# 04_POWER_V1-0.net
KiCad netlist of a schematic drawn in Altium Designer
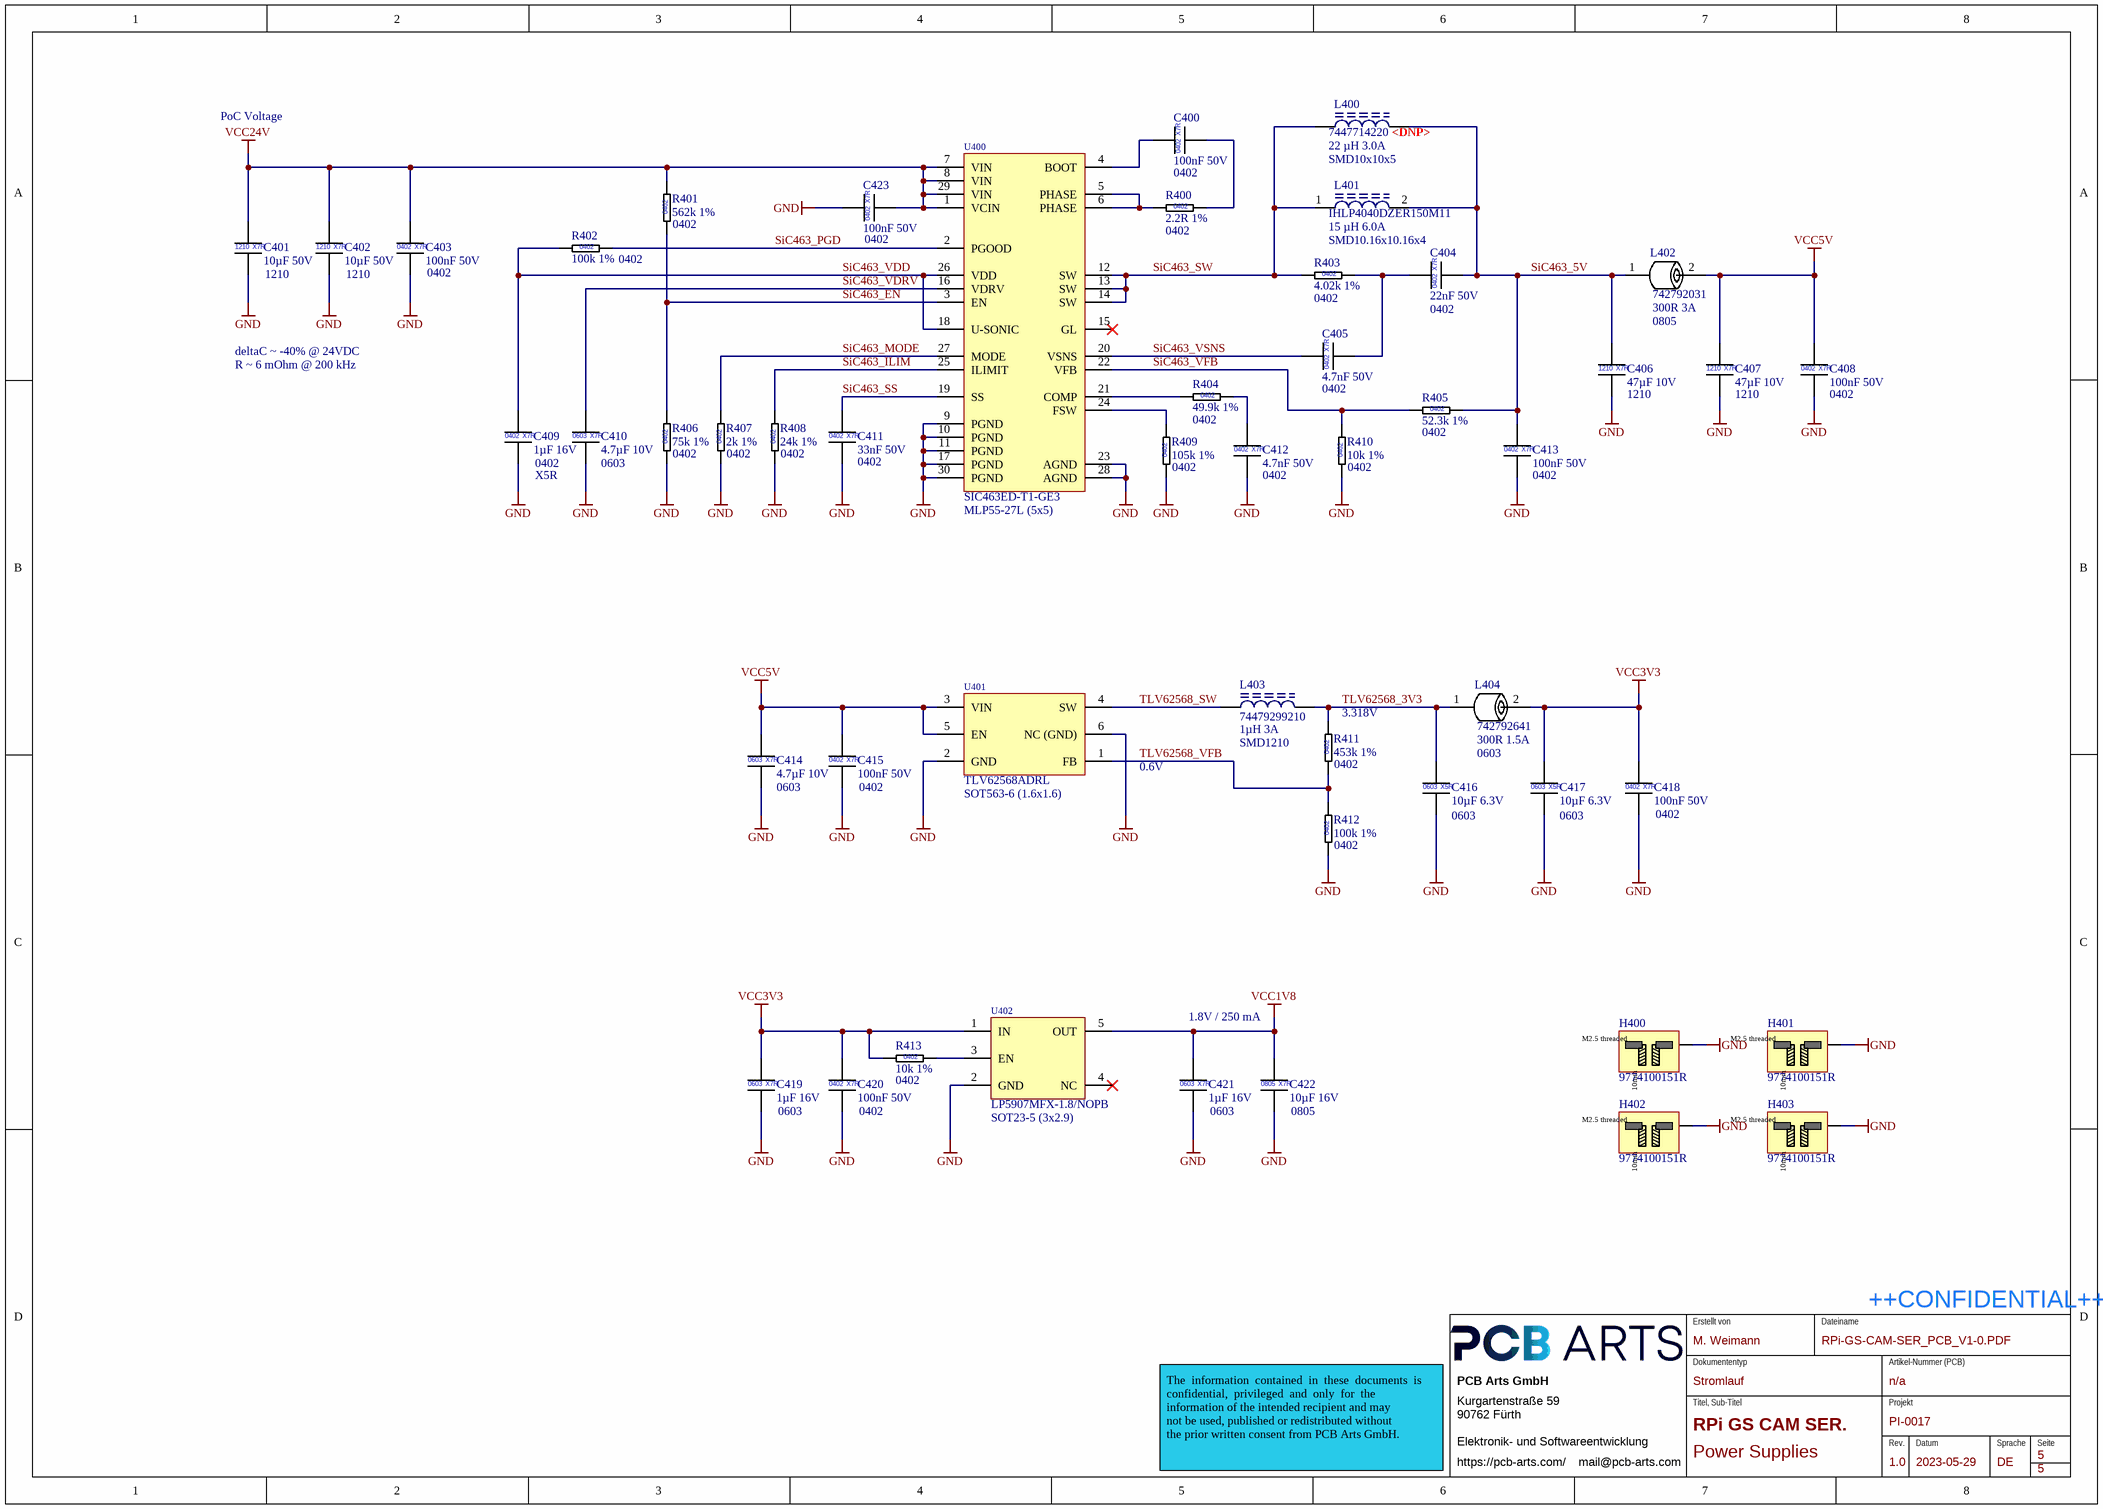
[diagram p0: 04_POWER_V1-0.SchDoc]

(export (version "E")
  (design (tool "Eeschema 10.0.6"))
  (components
    (comp (ref "C400")
      (value "100nF 50V")
      (footprint "Cap:CAP_0402_L")
      (description "Multilayer Ceramic Capacitors MLCC - SMD/SMT 0402 50VDC")
      (libsource (lib "") (part "CAP_0402_100nF_50V_1"))
    )
    (comp (ref "C401")
      (value "10µF 50V")
      (footprint "Cap:CAP_1210")
      (description "Multilayer Ceramic Capacitors MLCC - SMD/SMT 10 uF 50 VDC 10% 1210 X7R")
      (libsource (lib "Cap") (part "CAP_1210_10µF_50V_X7R_10%"))
    )
    (comp (ref "C402")
      (value "10µF 50V")
      (footprint "Cap:CAP_1210")
      (description "Multilayer Ceramic Capacitors MLCC - SMD/SMT 10 uF 50 VDC 10% 1210 X7R")
      (libsource (lib "Cap") (part "CAP_1210_10µF_50V_X7R_10%"))
    )
    (comp (ref "C403")
      (value "100nF 50V")
      (footprint "Cap:CAP_0402_L")
      (description "Multilayer Ceramic Capacitors MLCC - SMD/SMT 0402 50VDC")
      (libsource (lib "Cap") (part "CAP_0402_100nF_50V"))
    )
    (comp (ref "C404")
      (value "22nF 50V")
      (footprint "Cap:CAP_0402_L")
      (description "Multilayer Ceramic Capacitors MLCC - SMD/SMT 0402 50VDC")
      (libsource (lib "Cap") (part "CAP_0402_22nF_50V"))
    )
    (comp (ref "C405")
      (value "4.7nF 50V")
      (footprint "Cap:CAP_0402_L")
      (description "Multilayer Ceramic Capacitors MLCC - SMD/SMT 50V 0.022uF X7R 0402 10%")
      (libsource (lib "") (part "CAP_0402_4.7nF_50V_X7R_10%_1"))
    )
    (comp (ref "C406")
      (value "47µF 10V")
      (footprint "Cap:CAP_1210")
      (description "Multilayer Ceramic Capacitors MLCC - SMD/SMT 47 uF 10 VDC 10% 1210 X7R")
      (libsource (lib "Cap") (part "CAP_1210_47µF_10V_X7R_10%"))
    )
    (comp (ref "C407")
      (value "47µF 10V")
      (footprint "Cap:CAP_1210")
      (description "Multilayer Ceramic Capacitors MLCC - SMD/SMT 47 uF 10 VDC 10% 1210 X7R")
      (libsource (lib "Cap") (part "CAP_1210_47µF_10V_X7R_10%"))
    )
    (comp (ref "C408")
      (value "100nF 50V")
      (footprint "Cap:CAP_0402_L")
      (description "Multilayer Ceramic Capacitors MLCC - SMD/SMT 0402 50VDC")
      (libsource (lib "Cap") (part "CAP_0402_100nF_50V"))
    )
    (comp (ref "C409")
      (value "1µF 16V")
      (footprint "Cap:CAP_0402_L")
      (description "Multilayer Ceramic Capacitors MLCC - SMD/SMT 0402 16VDC")
      (libsource (lib "Cap") (part "CAP_0402_1µF_16V"))
    )
    (comp (ref "C410")
      (value "4.7µF 10V")
      (footprint "Cap:CAP_0603_L")
      (description "Multilayer Ceramic Capacitors MLCC - SMD/SMT 4.7 uF 10 VDC 10% 0603 X7R")
      (libsource (lib "Cap") (part "CAP_0603_4.7µF_10V_X7R_10%"))
    )
    (comp (ref "C411")
      (value "33nF 50V")
      (footprint "Cap:CAP_0402_L")
      (description "Multilayer Ceramic Capacitors MLCC - SMD/SMT 0402 50VDC")
      (libsource (lib "Cap") (part "CAP_0402_33nF_50V"))
    )
    (comp (ref "C412")
      (value "4.7nF 50V")
      (footprint "Cap:CAP_0402_L")
      (description "Multilayer Ceramic Capacitors MLCC - SMD/SMT 50V 0.022uF X7R 0402 10%")
      (libsource (lib "Cap") (part "CAP_0402_4.7nF_50V_X7R_10%"))
    )
    (comp (ref "C413")
      (value "100nF 50V")
      (footprint "Cap:CAP_0402_L")
      (description "Multilayer Ceramic Capacitors MLCC - SMD/SMT 0402 50VDC")
      (libsource (lib "Cap") (part "CAP_0402_100nF_50V"))
    )
    (comp (ref "C414")
      (value "4.7µF 10V")
      (footprint "Cap:CAP_0603_L")
      (description "Multilayer Ceramic Capacitors MLCC - SMD/SMT 4.7 uF 10 VDC 10% 0603 X7R")
      (libsource (lib "Cap") (part "CAP_0603_4.7µF_10V_X7R_10%"))
    )
    (comp (ref "C415")
      (value "100nF 50V")
      (footprint "Cap:CAP_0402_L")
      (description "Multilayer Ceramic Capacitors MLCC - SMD/SMT 0402 50VDC")
      (libsource (lib "Cap") (part "CAP_0402_100nF_50V"))
    )
    (comp (ref "C416")
      (value "10µF 6.3V")
      (footprint "Cap:CAP_0603_L")
      (description "Multilayer Ceramic Capacitors MLCC - SMD/SMT 0603 6.3VDC")
      (libsource (lib "Cap") (part "CAP_0603_10µF_6.3V"))
    )
    (comp (ref "C417")
      (value "10µF 6.3V")
      (footprint "Cap:CAP_0603_L")
      (description "Multilayer Ceramic Capacitors MLCC - SMD/SMT 0603 6.3VDC")
      (libsource (lib "Cap") (part "CAP_0603_10µF_6.3V"))
    )
    (comp (ref "C418")
      (value "100nF 50V")
      (footprint "Cap:CAP_0402_L")
      (description "Multilayer Ceramic Capacitors MLCC - SMD/SMT 0402 50VDC")
      (libsource (lib "Cap") (part "CAP_0402_100nF_50V"))
    )
    (comp (ref "C419")
      (value "1µF 16V")
      (footprint "CAP_0603_L")
      (description "Multilayer Ceramic Capacitors MLCC - SMD/SMT 0603 16VDC 1uF 10% X7R 0.8mm")
      (libsource (lib "Cap") (part "CAP_0603_1µF_16V_X7R_10%"))
    )
    (comp (ref "C420")
      (value "100nF 50V")
      (footprint "Cap:CAP_0402_L")
      (description "Multilayer Ceramic Capacitors MLCC - SMD/SMT 0402 50VDC")
      (libsource (lib "Cap") (part "CAP_0402_100nF_50V"))
    )
    (comp (ref "C421")
      (value "1µF 16V")
      (footprint "CAP_0603_L")
      (description "Multilayer Ceramic Capacitors MLCC - SMD/SMT 0603 16VDC 1uF 10% X7R 0.8mm")
      (libsource (lib "Cap") (part "CAP_0603_1µF_16V_X7R_10%"))
    )
    (comp (ref "C422")
      (value "10µF 16V")
      (footprint "Cap:CAP_0805")
      (description "Multilayer Ceramic Capacitors MLCC - SMD/SMT 16V 10uF X7R 0805 10%")
      (libsource (lib "Cap") (part "CAP_0805_10µF_16V_X7R_10%"))
    )
    (comp (ref "C423")
      (value "100nF 50V")
      (footprint "Cap:CAP_0402_L")
      (description "Multilayer Ceramic Capacitors MLCC - SMD/SMT 0402 50VDC")
      (libsource (lib "") (part "CAP_0402_100nF_50V_1"))
    )
    (comp (ref "H400")
      (value "9774100151R")
      (footprint "Electro_Mech:9774100151R")
      (description "Würth Standoff M2.5 h:10mm 9774050151R")
      (libsource (lib "Electro_Mech") (part "Würth Standoff M2.5 h{colon}10mm"))
    )
    (comp (ref "H401")
      (value "9774100151R")
      (footprint "Electro_Mech:9774100151R")
      (description "Würth Standoff M2.5 h:10mm 9774050151R")
      (libsource (lib "Electro_Mech") (part "Würth Standoff M2.5 h{colon}10mm"))
    )
    (comp (ref "H402")
      (value "9774100151R")
      (footprint "Electro_Mech:9774100151R")
      (description "Würth Standoff M2.5 h:10mm 9774050151R")
      (libsource (lib "Electro_Mech") (part "Würth Standoff M2.5 h{colon}10mm"))
    )
    (comp (ref "H403")
      (value "9774100151R")
      (footprint "Electro_Mech:9774100151R")
      (description "Würth Standoff M2.5 h:10mm 9774050151R")
      (libsource (lib "Electro_Mech") (part "Würth Standoff M2.5 h{colon}10mm"))
    )
    (comp (ref "L400")
      (value "7447714220")
      (footprint "WE-PD_1050")
      (description "Power Inductors - SMD WE-PD 22uH 3A DCR=50mOhms")
      (libsource (lib "Indc") (part "7447714220_22uH_20%_3.0A_50mΩ_SMD"))
    )
    (comp (ref "L401")
      (value "IHLP4040DZER150M11")
      (footprint "IHLP-4040DZ-11")
      (description "15uH ±20% 6A 45mΩ SMD,10.16x10.16x4mm Power Inductor")
      (libsource (lib "Indc") (part "IHLP4040DZER150M11_15uH_20%_6.0A_45mΩ_SMD"))
    )
    (comp (ref "L402")
      (value "742792031")
      (footprint "indc:L_0805")
      (description "Ferrite Beads WE-CBF 0805 200MHz 300Ohm 3000mA AEC-Q200")
      (libsource (lib "Indc") (part "742792031 _Ferrite_Beads_0805_300Ohms_3000mA"))
    )
    (comp (ref "L403")
      (value "74479299210")
      (footprint "WE-PMCI_1210")
      (description "Fixed Power Inductor - SMD WE-PMCI 1210 1.0uH 3A 38mOhms 30%Tol")
      (libsource (lib "Indc") (part "74479299210_Fixed_Inductors_1.0uH_30%_3A_SMD1210"))
    )
    (comp (ref "L404")
      (value "742792641")
      (footprint "Indc:L_0603")
      (description "Ferrite Beads WE-CBF 0603 100MHz 300Ohm 2000mA AEC-Q200")
      (libsource (lib "Indc") (part "742792641_Ferrite_Beads_0603_300Ohms_1500mA"))
    )
    (comp (ref "R400")
      (value "2.2R 1%")
      (footprint "Res:RES_0402_L")
      (description "Thick Film Resistors - SMD 2.2Ohm 1%")
      (libsource (lib "Res") (part "RES_0402_2.2R_1%"))
    )
    (comp (ref "R401")
      (value "562k 1%")
      (footprint "Res:RES_0402_L")
      (description "Thick Film Resistors - SMD 562kOhms 62.5mW 0402 1%")
      (libsource (lib "Res") (part "RES_0402_562k_1%"))
    )
    (comp (ref "R402")
      (value "100k 1%")
      (footprint "Res:RES_0402_L")
      (description "Thick Film Resistors - SMD 100kOhm 1%")
      (libsource (lib "Res") (part "RES_0402_100k_1%"))
    )
    (comp (ref "R403")
      (value "4.02k 1%")
      (footprint "Res:RES_0402_L")
      (description "Thick Film Resistors - SMD 4.02kOhm 1%")
      (libsource (lib "Res") (part "RES_0402_4.02k_1%"))
    )
    (comp (ref "R404")
      (value "49.9k 1%")
      (footprint "Res:RES_0402_L")
      (description "Thick Film Resistors - SMD 49.9kOhm 1%")
      (libsource (lib "Res") (part "RES_0402_49.9k_1%"))
    )
    (comp (ref "R405")
      (value "52.3k 1%")
      (footprint "Res:RES_0402_L")
      (description "Thick Film Resistors - SMD 52.3kOhm 1%")
      (libsource (lib "Res") (part "RES_0402_52.3k_1%"))
    )
    (comp (ref "R406")
      (value "75k 1%")
      (footprint "Res:RES_0402_L")
      (description "Thick Film Resistors - SMD 75kOhm 1%")
      (libsource (lib "Res") (part "RES_0402_75k_1%"))
    )
    (comp (ref "R407")
      (value "2k 1%")
      (footprint "Res:RES_0402_L")
      (description "Thick Film Resistors - SMD 2 kOhms 62.5mW 0402 1%")
      (libsource (lib "Res") (part "RES_0402_2k_1%"))
    )
    (comp (ref "R408")
      (value "24k 1%")
      (footprint "Res:RES_0402_L")
      (description "Thick Film Resistors - SMD 24kOhm 1%")
      (libsource (lib "Res") (part "RES_0402_24k_1%"))
    )
    (comp (ref "R409")
      (value "105k 1%")
      (footprint "Res:RES_0402_L")
      (description "Thick Film Resistors - SMD 105kOhm 1%")
      (libsource (lib "Res") (part "RES_0402_105k_1%"))
    )
    (comp (ref "R410")
      (value "10k 1%")
      (footprint "Res:RES_0402_L")
      (description "Thick Film Resistors - SMD 10kOhm 1%")
      (libsource (lib "Res") (part "RES_0402_10k_1%"))
    )
    (comp (ref "R411")
      (value "453k 1%")
      (footprint "RES_0402_L")
      (description "Thick Film Resistors - SMD 1/16watt 453Kohms 1%")
      (libsource (lib "Res") (part "RES_0402_453k_1%"))
    )
    (comp (ref "R412")
      (value "100k 1%")
      (footprint "Res:RES_0402_L")
      (description "Thick Film Resistors - SMD 100kOhm 1%")
      (libsource (lib "Res") (part "RES_0402_100k_1%"))
    )
    (comp (ref "R413")
      (value "10k 1%")
      (footprint "Res:RES_0402_L")
      (description "Thick Film Resistors - SMD 10kOhm 1%")
      (libsource (lib "Res") (part "RES_0402_10k_1%"))
    )
    (comp (ref "U400")
      (value "SIC463ED-T1-GE3")
      (footprint "VISHAY_MLP55-27L")
      (description "Switching Voltage Regulators 4A, 4.5-60V buck reg 100kHZ to 2MHz; 5 mm x 5 mm MLP55-27L package")
      (libsource (lib "Power") (part "SIC463ED-T1-GE3_Switching_Voltage_Regulator_4A"))
    )
    (comp (ref "U401")
      (value "TLV62568ADRL")
      (footprint "Power:SON50P150X80-6N")
      (description "Step Down Converter with Forced PWM in SOT563 Package")
      (libsource (lib "Power") (part "TLV62568ADRL_Step Down Converter 1A; 2A"))
    )
    (comp (ref "U402")
      (value "LP5907MFX-1.8/NOPB")
      (footprint "SOT95P285X140-5N")
      (description "LDO Spannungs-Regulator 250mA Ultra-Lo Noise LDO Reg SOT23-5")
      (libsource (lib "Power") (part "LP5907MFX-1.8/NOPB_LDO_Voltage_Regulators_250mA"))
    )
  )
  (nets
    (net (code "1") (name "/SiC463_5V") (class "Default")
      (node (ref "C404") (pin "2") (pinfunction "2_2") (pintype "passive"))
      (node (ref "C406") (pin "1") (pinfunction "1_1") (pintype "passive"))
      (node (ref "C413") (pin "1") (pinfunction "1_1") (pintype "passive"))
      (node (ref "L400") (pin "2") (pinfunction "2_2") (pintype "passive"))
      (node (ref "L401") (pin "2") (pinfunction "2_2") (pintype "passive"))
      (node (ref "L402") (pin "1") (pinfunction "1_1") (pintype "passive"))
      (node (ref "R405") (pin "2") (pinfunction "2_2") (pintype "passive"))
    )
    (net (code "2") (name "/SiC463_EN") (class "Default")
      (node (ref "R401") (pin "1") (pinfunction "1_1") (pintype "passive"))
      (node (ref "R406") (pin "2") (pinfunction "2_2") (pintype "passive"))
      (node (ref "U400") (pin "3") (pinfunction "EN_3") (pintype "passive"))
    )
    (net (code "3") (name "/SiC463_ILIM") (class "Default")
      (node (ref "R408") (pin "2") (pinfunction "2_2") (pintype "passive"))
      (node (ref "U400") (pin "25") (pinfunction "ILIMIT_25") (pintype "passive"))
    )
    (net (code "4") (name "/SiC463_MODE") (class "Default")
      (node (ref "R407") (pin "2") (pinfunction "2_2") (pintype "passive"))
      (node (ref "U400") (pin "27") (pinfunction "MODE_27") (pintype "passive"))
    )
    (net (code "5") (name "/SiC463_PGD") (class "Default")
      (node (ref "R402") (pin "2") (pinfunction "2_2") (pintype "passive"))
      (node (ref "U400") (pin "2") (pinfunction "PGOOD_2") (pintype "passive"))
    )
    (net (code "6") (name "/SiC463_SS") (class "Default")
      (node (ref "C411") (pin "1") (pinfunction "1_1") (pintype "passive"))
      (node (ref "U400") (pin "19") (pinfunction "SS_19") (pintype "passive"))
    )
    (net (code "7") (name "/SiC463_SW") (class "Default")
      (node (ref "L400") (pin "1") (pinfunction "1_1") (pintype "passive"))
      (node (ref "L401") (pin "1") (pinfunction "1_1") (pintype "passive"))
      (node (ref "R403") (pin "1") (pinfunction "1_1") (pintype "passive"))
      (node (ref "U400") (pin "12") (pinfunction "SW_12") (pintype "passive"))
      (node (ref "U400") (pin "13") (pinfunction "SW_13") (pintype "passive"))
      (node (ref "U400") (pin "14") (pinfunction "SW_14") (pintype "passive"))
    )
    (net (code "8") (name "/SiC463_VDD") (class "Default")
      (node (ref "C409") (pin "1") (pinfunction "1_1") (pintype "passive"))
      (node (ref "R402") (pin "1") (pinfunction "1_1") (pintype "passive"))
      (node (ref "U400") (pin "18") (pinfunction "U-SONIC_18") (pintype "passive"))
      (node (ref "U400") (pin "26") (pinfunction "VDD_26") (pintype "passive"))
    )
    (net (code "9") (name "/SiC463_VDRV") (class "Default")
      (node (ref "C410") (pin "1") (pinfunction "1_1") (pintype "passive"))
      (node (ref "U400") (pin "16") (pinfunction "VDRV_16") (pintype "passive"))
    )
    (net (code "10") (name "/SiC463_VFB") (class "Default")
      (node (ref "R405") (pin "1") (pinfunction "1_1") (pintype "passive"))
      (node (ref "R410") (pin "2") (pinfunction "2_2") (pintype "passive"))
      (node (ref "U400") (pin "22") (pinfunction "VFB_22") (pintype "passive"))
    )
    (net (code "11") (name "/SiC463_VSNS") (class "Default")
      (node (ref "C405") (pin "1") (pinfunction "1_1") (pintype "passive"))
      (node (ref "U400") (pin "20") (pinfunction "VSNS_20") (pintype "passive"))
    )
    (net (code "12") (name "/TLV62568_3V3") (class "Default")
      (node (ref "C416") (pin "1") (pinfunction "1_1") (pintype "passive"))
      (node (ref "L403") (pin "2") (pinfunction "2_2") (pintype "passive"))
      (node (ref "L404") (pin "1") (pinfunction "1_1") (pintype "passive"))
      (node (ref "R411") (pin "2") (pinfunction "2_2") (pintype "passive"))
    )
    (net (code "13") (name "/TLV62568_SW") (class "Default")
      (node (ref "L403") (pin "1") (pinfunction "1_1") (pintype "passive"))
      (node (ref "U401") (pin "4") (pinfunction "SW_4") (pintype "passive"))
    )
    (net (code "14") (name "/TLV62568_VFB") (class "Default")
      (node (ref "R411") (pin "1") (pinfunction "1_1") (pintype "passive"))
      (node (ref "R412") (pin "2") (pinfunction "2_2") (pintype "passive"))
      (node (ref "U401") (pin "1") (pinfunction "FB_1") (pintype "passive"))
    )
    (net (code "15") (name "GND") (class "Default")
      (node (ref "C401") (pin "2") (pinfunction "2_2") (pintype "passive"))
      (node (ref "C402") (pin "2") (pinfunction "2_2") (pintype "passive"))
      (node (ref "C403") (pin "2") (pinfunction "2_2") (pintype "passive"))
      (node (ref "C406") (pin "2") (pinfunction "2_2") (pintype "passive"))
      (node (ref "C407") (pin "2") (pinfunction "2_2") (pintype "passive"))
      (node (ref "C408") (pin "2") (pinfunction "2_2") (pintype "passive"))
      (node (ref "C409") (pin "2") (pinfunction "2_2") (pintype "passive"))
      (node (ref "C410") (pin "2") (pinfunction "2_2") (pintype "passive"))
      (node (ref "C411") (pin "2") (pinfunction "2_2") (pintype "passive"))
      (node (ref "C412") (pin "2") (pinfunction "2_2") (pintype "passive"))
      (node (ref "C413") (pin "2") (pinfunction "2_2") (pintype "passive"))
      (node (ref "C414") (pin "2") (pinfunction "2_2") (pintype "passive"))
      (node (ref "C415") (pin "2") (pinfunction "2_2") (pintype "passive"))
      (node (ref "C416") (pin "2") (pinfunction "2_2") (pintype "passive"))
      (node (ref "C417") (pin "2") (pinfunction "2_2") (pintype "passive"))
      (node (ref "C418") (pin "2") (pinfunction "2_2") (pintype "passive"))
      (node (ref "C419") (pin "2") (pinfunction "2_2") (pintype "passive"))
      (node (ref "C420") (pin "2") (pinfunction "2_2") (pintype "passive"))
      (node (ref "C421") (pin "2") (pinfunction "2_2") (pintype "passive"))
      (node (ref "C422") (pin "2") (pinfunction "2_2") (pintype "passive"))
      (node (ref "C423") (pin "1") (pinfunction "1_1") (pintype "passive"))
      (node (ref "H400") (pin "1") (pinfunction "1_1") (pintype "passive"))
      (node (ref "H401") (pin "1") (pinfunction "1_1") (pintype "passive"))
      (node (ref "H402") (pin "1") (pinfunction "1_1") (pintype "passive"))
      (node (ref "H403") (pin "1") (pinfunction "1_1") (pintype "passive"))
      (node (ref "R406") (pin "1") (pinfunction "1_1") (pintype "passive"))
      (node (ref "R407") (pin "1") (pinfunction "1_1") (pintype "passive"))
      (node (ref "R408") (pin "1") (pinfunction "1_1") (pintype "passive"))
      (node (ref "R409") (pin "1") (pinfunction "1_1") (pintype "passive"))
      (node (ref "R410") (pin "1") (pinfunction "1_1") (pintype "passive"))
      (node (ref "R412") (pin "1") (pinfunction "1_1") (pintype "passive"))
      (node (ref "U400") (pin "10") (pinfunction "PGND_10") (pintype "passive"))
      (node (ref "U400") (pin "11") (pinfunction "PGND_11") (pintype "passive"))
      (node (ref "U400") (pin "17") (pinfunction "PGND_17") (pintype "passive"))
      (node (ref "U400") (pin "23") (pinfunction "AGND_23") (pintype "passive"))
      (node (ref "U400") (pin "28") (pinfunction "AGND_28") (pintype "passive"))
      (node (ref "U400") (pin "30") (pinfunction "PGND_30") (pintype "passive"))
      (node (ref "U400") (pin "9") (pinfunction "PGND_9") (pintype "passive"))
      (node (ref "U401") (pin "2") (pinfunction "GND_2") (pintype "passive"))
      (node (ref "U401") (pin "6") (pinfunction "NC_(GND)_6") (pintype "passive"))
      (node (ref "U402") (pin "2") (pinfunction "GND_2") (pintype "passive"))
    )
    (net (code "16") (name "Net-(C400-Pad2)") (class "Default")
      (node (ref "C400") (pin "2") (pinfunction "2_2") (pintype "passive"))
      (node (ref "R400") (pin "2") (pinfunction "2_2") (pintype "passive"))
    )
    (net (code "17") (name "Net-(C404-Pad1)") (class "Default")
      (node (ref "C404") (pin "1") (pinfunction "1_1") (pintype "passive"))
      (node (ref "C405") (pin "2") (pinfunction "2_2") (pintype "passive"))
      (node (ref "R403") (pin "2") (pinfunction "2_2") (pintype "passive"))
    )
    (net (code "18") (name "Net-(C412-Pad1)") (class "Default")
      (node (ref "C412") (pin "1") (pinfunction "1_1") (pintype "passive"))
      (node (ref "R404") (pin "2") (pinfunction "2_2") (pintype "passive"))
    )
    (net (code "19") (name "Net-(R400-Pad1)") (class "Default")
      (node (ref "R400") (pin "1") (pinfunction "1_1") (pintype "passive"))
      (node (ref "U400") (pin "5") (pinfunction "PHASE_5") (pintype "passive"))
      (node (ref "U400") (pin "6") (pinfunction "PHASE_6") (pintype "passive"))
    )
    (net (code "20") (name "Net-(U400-BOOT)") (class "Default")
      (node (ref "C400") (pin "1") (pinfunction "1_1") (pintype "passive"))
      (node (ref "U400") (pin "4") (pinfunction "BOOT_4") (pintype "passive"))
    )
    (net (code "21") (name "Net-(U400-COMP)") (class "Default")
      (node (ref "R404") (pin "1") (pinfunction "1_1") (pintype "passive"))
      (node (ref "U400") (pin "21") (pinfunction "COMP_21") (pintype "passive"))
    )
    (net (code "22") (name "Net-(U400-FSW)") (class "Default")
      (node (ref "R409") (pin "2") (pinfunction "2_2") (pintype "passive"))
      (node (ref "U400") (pin "24") (pinfunction "FSW_24") (pintype "passive"))
    )
    (net (code "23") (name "Net-(U402-EN)") (class "Default")
      (node (ref "R413") (pin "2") (pinfunction "2_2") (pintype "passive"))
      (node (ref "U402") (pin "3") (pinfunction "EN_3") (pintype "passive"))
    )
    (net (code "24") (name "VCC1V8") (class "Default")
      (node (ref "C421") (pin "1") (pinfunction "1_1") (pintype "passive"))
      (node (ref "C422") (pin "1") (pinfunction "1_1") (pintype "passive"))
      (node (ref "U402") (pin "5") (pinfunction "OUT_5") (pintype "passive"))
    )
    (net (code "25") (name "VCC3V3") (class "Default")
      (node (ref "C417") (pin "1") (pinfunction "1_1") (pintype "passive"))
      (node (ref "C418") (pin "1") (pinfunction "1_1") (pintype "passive"))
      (node (ref "C419") (pin "1") (pinfunction "1_1") (pintype "passive"))
      (node (ref "C420") (pin "1") (pinfunction "1_1") (pintype "passive"))
      (node (ref "L404") (pin "2") (pinfunction "2_2") (pintype "passive"))
      (node (ref "R413") (pin "1") (pinfunction "1_1") (pintype "passive"))
      (node (ref "U402") (pin "1") (pinfunction "IN_1") (pintype "passive"))
    )
    (net (code "26") (name "VCC5V") (class "Default")
      (node (ref "C407") (pin "1") (pinfunction "1_1") (pintype "passive"))
      (node (ref "C408") (pin "1") (pinfunction "1_1") (pintype "passive"))
      (node (ref "C414") (pin "1") (pinfunction "1_1") (pintype "passive"))
      (node (ref "C415") (pin "1") (pinfunction "1_1") (pintype "passive"))
      (node (ref "L402") (pin "2") (pinfunction "2_2") (pintype "passive"))
      (node (ref "U401") (pin "3") (pinfunction "VIN_3") (pintype "passive"))
      (node (ref "U401") (pin "5") (pinfunction "EN_5") (pintype "passive"))
    )
    (net (code "27") (name "VCC24V") (class "Default")
      (node (ref "C401") (pin "1") (pinfunction "1_1") (pintype "passive"))
      (node (ref "C402") (pin "1") (pinfunction "1_1") (pintype "passive"))
      (node (ref "C403") (pin "1") (pinfunction "1_1") (pintype "passive"))
      (node (ref "C423") (pin "2") (pinfunction "2_2") (pintype "passive"))
      (node (ref "R401") (pin "2") (pinfunction "2_2") (pintype "passive"))
      (node (ref "U400") (pin "1") (pinfunction "VCIN_1") (pintype "passive"))
      (node (ref "U400") (pin "29") (pinfunction "VIN_29") (pintype "passive"))
      (node (ref "U400") (pin "7") (pinfunction "VIN_7") (pintype "passive"))
      (node (ref "U400") (pin "8") (pinfunction "VIN_8") (pintype "passive"))
    )
    (net (code "28") (name "unconnected-(U400-GL-Pad15)") (class "Default")
      (node (ref "U400") (pin "15") (pinfunction "GL_15") (pintype "passive+no_connect"))
    )
    (net (code "29") (name "unconnected-(U402-NC-Pad4)") (class "Default")
      (node (ref "U402") (pin "4") (pinfunction "NC_4") (pintype "passive+no_connect"))
    )
  )
)
